# SoC_ADC_DAC.net
KiCad netlist of a schematic drawn in Altium Designer
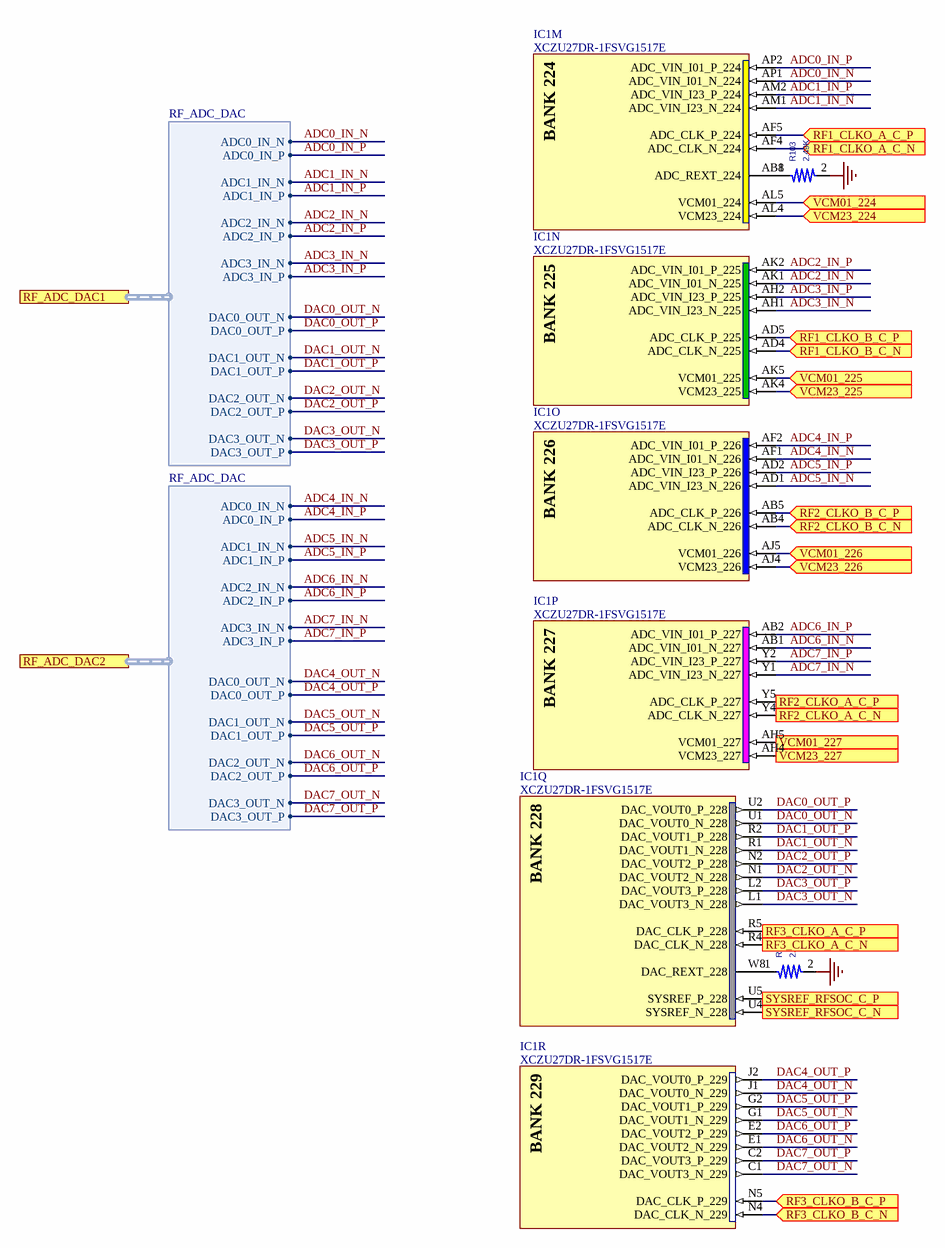
[diagram p0: SoC_ADC_DAC.SchDoc]

(export (version "E")
  (design (tool "Eeschema 10.0.6"))
  (components
    (comp (ref "IC1")
      (value "XCZU27DR-1FSVG1517E")
      (footprint "XILINX_FSVG1517 (XCZU27DR)")
      (fields (field (name "MANUFACTURER") "XILINX") (field (name "AUTHOR") "CERN DEM MR"))
      (libsource (lib "ICs And Semiconductors") (part "XCZU27DR-1FSVG1517E"))
    )
    (comp (ref "R103")
      (value "2.49K")
      (footprint "0402")
      (fields
        (field (name "POWER") "1/10W")
        (field (name "TOLERANCE") "1%")
        (field (name "MANF") "PANASONIC")
        (field (name "OWNER") "10460")
      )
      (libsource (lib "*") (part "RES"))
    )
    (comp (ref "R104")
      (value "2.49K")
      (footprint "0402")
      (fields
        (field (name "POWER") "1/10W")
        (field (name "TOLERANCE") "1%")
        (field (name "MANF") "PANASONIC")
        (field (name "OWNER") "10460")
      )
      (libsource (lib "*") (part "RES"))
    )
  )
  (nets
    (net (code "2") (name "/ADC0_IN_N") (class "Default")
      (node (ref "IC1") (pin "AP1") (pinfunction "ADC_VIN_I01_N_224_AP1") (pintype "input"))
    )
    (net (code "3") (name "/ADC0_IN_P") (class "Default")
      (node (ref "IC1") (pin "AP2") (pinfunction "ADC_VIN_I01_P_224_AP2") (pintype "input"))
    )
    (net (code "4") (name "/ADC1_IN_N") (class "Default")
      (node (ref "IC1") (pin "AM1") (pinfunction "ADC_VIN_I23_N_224_AM1") (pintype "input"))
    )
    (net (code "5") (name "/ADC1_IN_P") (class "Default")
      (node (ref "IC1") (pin "AM2") (pinfunction "ADC_VIN_I23_P_224_AM2") (pintype "input"))
    )
    (net (code "6") (name "/ADC2_IN_N") (class "Default")
      (node (ref "IC1") (pin "AK1") (pinfunction "ADC_VIN_I01_N_225_AK1") (pintype "input"))
    )
    (net (code "7") (name "/ADC2_IN_P") (class "Default")
      (node (ref "IC1") (pin "AK2") (pinfunction "ADC_VIN_I01_P_225_AK2") (pintype "input"))
    )
    (net (code "8") (name "/ADC3_IN_N") (class "Default")
      (node (ref "IC1") (pin "AH1") (pinfunction "ADC_VIN_I23_N_225_AH1") (pintype "input"))
    )
    (net (code "9") (name "/ADC3_IN_P") (class "Default")
      (node (ref "IC1") (pin "AH2") (pinfunction "ADC_VIN_I23_P_225_AH2") (pintype "input"))
    )
    (net (code "10") (name "/ADC4_IN_N") (class "Default")
      (node (ref "IC1") (pin "AF1") (pinfunction "ADC_VIN_I01_N_226_AF1") (pintype "input"))
    )
    (net (code "11") (name "/ADC4_IN_P") (class "Default")
      (node (ref "IC1") (pin "AF2") (pinfunction "ADC_VIN_I01_P_226_AF2") (pintype "input"))
    )
    (net (code "12") (name "/ADC5_IN_N") (class "Default")
      (node (ref "IC1") (pin "AD1") (pinfunction "ADC_VIN_I23_N_226_AD1") (pintype "input"))
    )
    (net (code "13") (name "/ADC5_IN_P") (class "Default")
      (node (ref "IC1") (pin "AD2") (pinfunction "ADC_VIN_I23_P_226_AD2") (pintype "input"))
    )
    (net (code "14") (name "/ADC6_IN_N") (class "Default")
      (node (ref "IC1") (pin "AB1") (pinfunction "ADC_VIN_I01_N_227_AB1") (pintype "input"))
    )
    (net (code "15") (name "/ADC6_IN_P") (class "Default")
      (node (ref "IC1") (pin "AB2") (pinfunction "ADC_VIN_I01_P_227_AB2") (pintype "input"))
    )
    (net (code "16") (name "/ADC7_IN_N") (class "Default")
      (node (ref "IC1") (pin "Y1") (pinfunction "ADC_VIN_I23_N_227_Y1") (pintype "input"))
    )
    (net (code "17") (name "/ADC7_IN_P") (class "Default")
      (node (ref "IC1") (pin "Y2") (pinfunction "ADC_VIN_I23_P_227_Y2") (pintype "input"))
    )
    (net (code "18") (name "/DAC0_OUT_N") (class "Default")
      (node (ref "IC1") (pin "U1") (pinfunction "DAC_VOUT0_N_228_U1") (pintype "output"))
    )
    (net (code "19") (name "/DAC0_OUT_P") (class "Default")
      (node (ref "IC1") (pin "U2") (pinfunction "DAC_VOUT0_P_228_U2") (pintype "output"))
    )
    (net (code "20") (name "/DAC1_OUT_N") (class "Default")
      (node (ref "IC1") (pin "R1") (pinfunction "DAC_VOUT1_N_228_R1") (pintype "output"))
    )
    (net (code "21") (name "/DAC1_OUT_P") (class "Default")
      (node (ref "IC1") (pin "R2") (pinfunction "DAC_VOUT1_P_228_R2") (pintype "output"))
    )
    (net (code "22") (name "/DAC2_OUT_N") (class "Default")
      (node (ref "IC1") (pin "N1") (pinfunction "DAC_VOUT2_N_228_N1") (pintype "output"))
    )
    (net (code "23") (name "/DAC2_OUT_P") (class "Default")
      (node (ref "IC1") (pin "N2") (pinfunction "DAC_VOUT2_P_228_N2") (pintype "output"))
    )
    (net (code "24") (name "/DAC3_OUT_N") (class "Default")
      (node (ref "IC1") (pin "L1") (pinfunction "DAC_VOUT3_N_228_L1") (pintype "output"))
    )
    (net (code "25") (name "/DAC3_OUT_P") (class "Default")
      (node (ref "IC1") (pin "L2") (pinfunction "DAC_VOUT3_P_228_L2") (pintype "output"))
    )
    (net (code "26") (name "/DAC4_OUT_N") (class "Default")
      (node (ref "IC1") (pin "J1") (pinfunction "DAC_VOUT0_N_229_J1") (pintype "output"))
    )
    (net (code "27") (name "/DAC4_OUT_P") (class "Default")
      (node (ref "IC1") (pin "J2") (pinfunction "DAC_VOUT0_P_229_J2") (pintype "output"))
    )
    (net (code "28") (name "/DAC5_OUT_N") (class "Default")
      (node (ref "IC1") (pin "G1") (pinfunction "DAC_VOUT1_N_229_G1") (pintype "output"))
    )
    (net (code "29") (name "/DAC5_OUT_P") (class "Default")
      (node (ref "IC1") (pin "G2") (pinfunction "DAC_VOUT1_P_229_G2") (pintype "output"))
    )
    (net (code "30") (name "/DAC6_OUT_N") (class "Default")
      (node (ref "IC1") (pin "E1") (pinfunction "DAC_VOUT2_N_229_E1") (pintype "output"))
    )
    (net (code "31") (name "/DAC6_OUT_P") (class "Default")
      (node (ref "IC1") (pin "E2") (pinfunction "DAC_VOUT2_P_229_E2") (pintype "output"))
    )
    (net (code "32") (name "/DAC7_OUT_N") (class "Default")
      (node (ref "IC1") (pin "C1") (pinfunction "DAC_VOUT3_N_229_C1") (pintype "output"))
    )
    (net (code "33") (name "/DAC7_OUT_P") (class "Default")
      (node (ref "IC1") (pin "C2") (pinfunction "DAC_VOUT3_P_229_C2") (pintype "output"))
    )
    (net (code "34") (name "/RF1_CLKO_A_C_N") (class "Default")
      (node (ref "IC1") (pin "AF4") (pinfunction "ADC_CLK_N_224_AF4") (pintype "input"))
    )
    (net (code "35") (name "/RF1_CLKO_A_C_P") (class "Default")
      (node (ref "IC1") (pin "AF5") (pinfunction "ADC_CLK_P_224_AF5") (pintype "input"))
    )
    (net (code "36") (name "/RF1_CLKO_B_C_N") (class "Default")
      (node (ref "IC1") (pin "AD4") (pinfunction "ADC_CLK_N_225_AD4") (pintype "input"))
    )
    (net (code "37") (name "/RF1_CLKO_B_C_P") (class "Default")
      (node (ref "IC1") (pin "AD5") (pinfunction "ADC_CLK_P_225_AD5") (pintype "input"))
    )
    (net (code "38") (name "/RF2_CLKO_A_C_N") (class "Default")
      (node (ref "IC1") (pin "Y4") (pinfunction "ADC_CLK_N_227_Y4") (pintype "input"))
    )
    (net (code "39") (name "/RF2_CLKO_A_C_P") (class "Default")
      (node (ref "IC1") (pin "Y5") (pinfunction "ADC_CLK_P_227_Y5") (pintype "input"))
    )
    (net (code "40") (name "/RF2_CLKO_B_C_N") (class "Default")
      (node (ref "IC1") (pin "AB4") (pinfunction "ADC_CLK_N_226_AB4") (pintype "input"))
    )
    (net (code "41") (name "/RF2_CLKO_B_C_P") (class "Default")
      (node (ref "IC1") (pin "AB5") (pinfunction "ADC_CLK_P_226_AB5") (pintype "input"))
    )
    (net (code "42") (name "/RF3_CLKO_A_C_N") (class "Default")
      (node (ref "IC1") (pin "R4") (pinfunction "DAC_CLK_N_228_R4") (pintype "input"))
    )
    (net (code "43") (name "/RF3_CLKO_A_C_P") (class "Default")
      (node (ref "IC1") (pin "R5") (pinfunction "DAC_CLK_P_228_R5") (pintype "input"))
    )
    (net (code "44") (name "/RF3_CLKO_B_C_N") (class "Default")
      (node (ref "IC1") (pin "N4") (pinfunction "DAC_CLK_N_229_N4") (pintype "input"))
    )
    (net (code "45") (name "/RF3_CLKO_B_C_P") (class "Default")
      (node (ref "IC1") (pin "N5") (pinfunction "DAC_CLK_P_229_N5") (pintype "input"))
    )
    (net (code "46") (name "/SYSREF_RFSOC_C_N") (class "Default")
      (node (ref "IC1") (pin "U4") (pinfunction "SYSREF_N_228_U4") (pintype "input"))
    )
    (net (code "47") (name "/SYSREF_RFSOC_C_P") (class "Default")
      (node (ref "IC1") (pin "U5") (pinfunction "SYSREF_P_228_U5") (pintype "input"))
    )
    (net (code "48") (name "/VCM01_224") (class "Default")
      (node (ref "IC1") (pin "AL5") (pinfunction "VCM01_224_AL5") (pintype "input"))
    )
    (net (code "49") (name "/VCM01_225") (class "Default")
      (node (ref "IC1") (pin "AK5") (pinfunction "VCM01_225_AK5") (pintype "input"))
    )
    (net (code "50") (name "/VCM01_226") (class "Default")
      (node (ref "IC1") (pin "AJ5") (pinfunction "VCM01_226_AJ5") (pintype "input"))
    )
    (net (code "51") (name "/VCM01_227") (class "Default")
      (node (ref "IC1") (pin "AH5") (pinfunction "VCM01_227_AH5") (pintype "input"))
    )
    (net (code "52") (name "/VCM23_224") (class "Default")
      (node (ref "IC1") (pin "AL4") (pinfunction "VCM23_224_AL4") (pintype "input"))
    )
    (net (code "53") (name "/VCM23_225") (class "Default")
      (node (ref "IC1") (pin "AK4") (pinfunction "VCM23_225_AK4") (pintype "input"))
    )
    (net (code "54") (name "/VCM23_226") (class "Default")
      (node (ref "IC1") (pin "AJ4") (pinfunction "VCM23_226_AJ4") (pintype "input"))
    )
    (net (code "55") (name "/VCM23_227") (class "Default")
      (node (ref "IC1") (pin "AH4") (pinfunction "VCM23_227_AH4") (pintype "input"))
    )
    (net (code "57") (name "GND") (class "Default")
      (node (ref "R103") (pin "2") (pinfunction "2_2") (pintype "passive"))
      (node (ref "R104") (pin "2") (pinfunction "2_2") (pintype "passive"))
    )
    (net (code "58") (name "Net-(IC1M-ADC_REXT_224)") (class "Default")
      (node (ref "IC1") (pin "AB8") (pinfunction "ADC_REXT_224_AB8") (pintype "passive"))
      (node (ref "R103") (pin "1") (pinfunction "1_1") (pintype "passive"))
    )
    (net (code "59") (name "Net-(IC1Q-DAC_REXT_228)") (class "Default")
      (node (ref "IC1") (pin "W8") (pinfunction "DAC_REXT_228_W8") (pintype "passive"))
      (node (ref "R104") (pin "1") (pinfunction "1_1") (pintype "passive"))
    )
  )
)
